# USB.net
KiCad netlist of a schematic drawn in Altium Designer
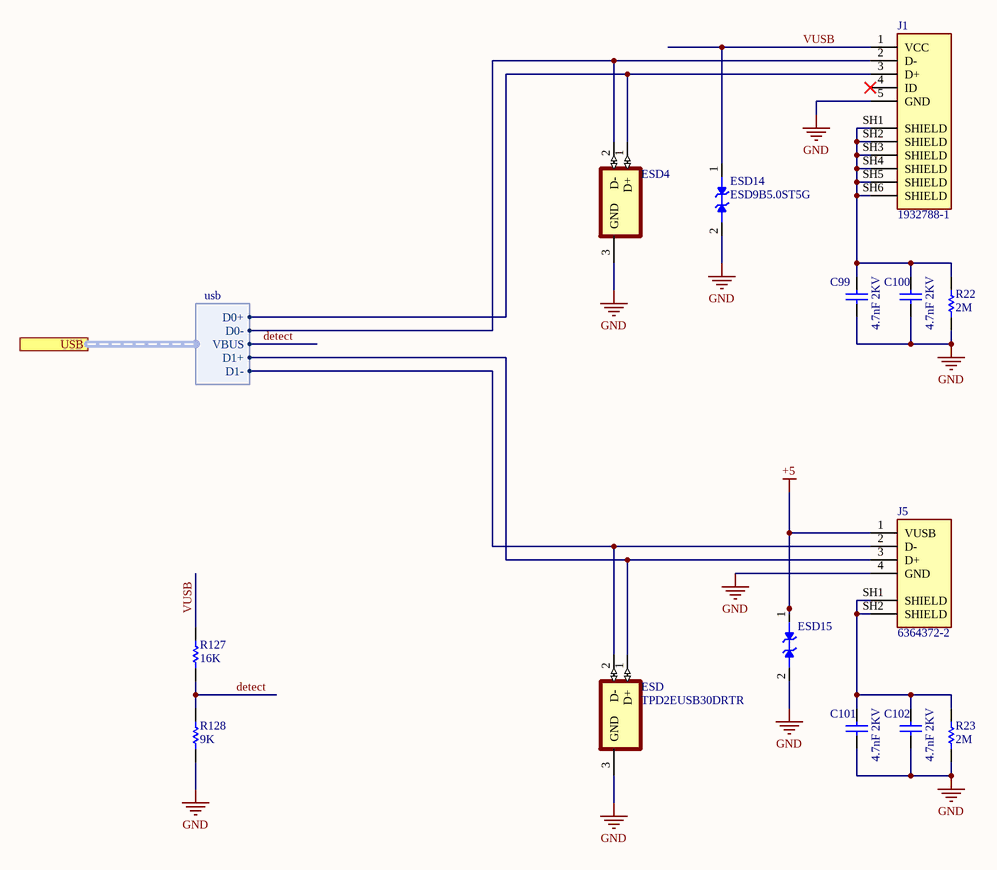
[diagram p0: USB.SchDoc]

(export (version "E")
  (design (tool "Eeschema 10.0.6"))
  (components
    (comp (ref "C99")
      (value "4.7nF 2KV")
      (footprint "C1210")
      (fields (field (name "Comment") "C1210"))
      (libsource (lib "kit") (part "C1210"))
    )
    (comp (ref "C100")
      (value "4.7nF 2KV")
      (footprint "C1210")
      (fields (field (name "Comment") "C1210"))
      (libsource (lib "kit") (part "C1210"))
    )
    (comp (ref "C101")
      (value "4.7nF 2KV")
      (footprint "C1210")
      (fields (field (name "Comment") "C1210"))
      (libsource (lib "kit") (part "C1210"))
    )
    (comp (ref "C102")
      (value "4.7nF 2KV")
      (footprint "C1210")
      (fields (field (name "Comment") "C1210"))
      (libsource (lib "kit") (part "C1210"))
    )
    (comp (ref "ESD")
      (value "TPD2EUSB30DRTR")
      (footprint "SOTFL35P100X50-3N")
      (description "2-channel ESD solution for SuperSpeed USB 3.0 interface 3-SOT-9X3 -40 to 85")
      (libsource (lib "kit") (part "TPD2EUSB30DRTR"))
    )
    (comp (ref "ESD4")
      (value "TPD2EUSB30DRTR")
      (footprint "SOTFL35P100X50-3N")
      (description "2-channel ESD solution for SuperSpeed USB 3.0 interface 3-SOT-9X3 -40 to 85")
      (libsource (lib "kit") (part "TPD2EUSB30DRTR"))
    )
    (comp (ref "ESD14")
      (value "ESD9B5.0ST5G")
      (footprint "SODFL1006X40N")
      (description "Clamp Ipp Tvs Diode Surface Mount SOD-923")
      (libsource (lib "kit") (part "ESD9B5.0ST5G"))
    )
    (comp (ref "ESD15")
      (value "ESD9B5.0ST5G")
      (footprint "SODFL1006X40N")
      (description "Clamp Ipp Tvs Diode Surface Mount SOD-923")
      (libsource (lib "kit") (part "ESD9B5.0ST5G"))
    )
    (comp (ref "J1")
      (value "1932788-1")
      (footprint "TE_1932788-1")
      (libsource (lib "kit") (part "1932788-1"))
    )
    (comp (ref "J5")
      (value "6364372-2")
      (footprint "TE_6364372-2")
      (libsource (lib "kit") (part "6364372-2"))
    )
    (comp (ref "R22")
      (value "2M")
      (footprint "R0603")
      (fields (field (name "Comment") "R0603"))
      (libsource (lib "kit") (part "R0603"))
    )
    (comp (ref "R23")
      (value "2M")
      (footprint "R0603")
      (fields (field (name "Comment") "R0603"))
      (libsource (lib "kit") (part "R0603"))
    )
    (comp (ref "R127")
      (value "16K")
      (footprint "R0603")
      (fields (field (name "Comment") "R0603"))
      (libsource (lib "kit") (part "R0603"))
    )
    (comp (ref "R128")
      (value "9K")
      (footprint "R0603")
      (fields (field (name "Comment") "R0603"))
      (libsource (lib "kit") (part "R0603"))
    )
  )
  (nets
    (net (code "2") (name "+5") (class "Default")
      (node (ref "ESD15") (pin "1") (pinfunction "A_1") (pintype "passive"))
      (node (ref "J5") (pin "1") (pinfunction "VUSB_1") (pintype "passive"))
    )
    (net (code "3") (name "/VUSB") (class "Default")
      (node (ref "ESD14") (pin "1") (pinfunction "A_1") (pintype "passive"))
      (node (ref "J1") (pin "1") (pinfunction "VCC_1") (pintype "power_in"))
      (node (ref "R127") (pin "2") (pinfunction "2_2") (pintype "passive"))
    )
    (net (code "4") (name "/detect") (class "Default")
      (node (ref "R127") (pin "1") (pinfunction "1_1") (pintype "passive"))
      (node (ref "R128") (pin "2") (pinfunction "2_2") (pintype "passive"))
    )
    (net (code "6") (name "GND") (class "Default")
      (node (ref "C100") (pin "1") (pinfunction "1_1") (pintype "passive"))
      (node (ref "C101") (pin "1") (pinfunction "1_1") (pintype "passive"))
      (node (ref "C102") (pin "1") (pinfunction "1_1") (pintype "passive"))
      (node (ref "C99") (pin "1") (pinfunction "1_1") (pintype "passive"))
      (node (ref "ESD") (pin "3") (pinfunction "GND_3") (pintype "power_in"))
      (node (ref "ESD14") (pin "2") (pinfunction "A1_2") (pintype "passive"))
      (node (ref "ESD15") (pin "2") (pinfunction "A1_2") (pintype "passive"))
      (node (ref "ESD4") (pin "3") (pinfunction "GND_3") (pintype "power_in"))
      (node (ref "J1") (pin "5") (pinfunction "GND_5") (pintype "power_in"))
      (node (ref "J5") (pin "4") (pinfunction "GND_4") (pintype "passive"))
      (node (ref "R128") (pin "1") (pinfunction "1_1") (pintype "passive"))
      (node (ref "R22") (pin "2") (pinfunction "2_2") (pintype "passive"))
      (node (ref "R23") (pin "2") (pinfunction "2_2") (pintype "passive"))
    )
    (net (code "7") (name "Net-(C100-Pad2)") (class "Default")
      (node (ref "C100") (pin "2") (pinfunction "2_2") (pintype "passive"))
      (node (ref "C99") (pin "2") (pinfunction "2_2") (pintype "passive"))
      (node (ref "J1") (pin "SH1") (pinfunction "SHIELD_SH1") (pintype "passive"))
      (node (ref "J1") (pin "SH2") (pinfunction "SHIELD_SH2") (pintype "passive"))
      (node (ref "J1") (pin "SH3") (pinfunction "SHIELD_SH3") (pintype "passive"))
      (node (ref "J1") (pin "SH4") (pinfunction "SHIELD_SH4") (pintype "passive"))
      (node (ref "J1") (pin "SH5") (pinfunction "SHIELD_SH5") (pintype "passive"))
      (node (ref "J1") (pin "SH6") (pinfunction "SHIELD_SH6") (pintype "passive"))
      (node (ref "R22") (pin "1") (pinfunction "1_1") (pintype "passive"))
    )
    (net (code "8") (name "Net-(C101-Pad2)") (class "Default")
      (node (ref "C101") (pin "2") (pinfunction "2_2") (pintype "passive"))
      (node (ref "C102") (pin "2") (pinfunction "2_2") (pintype "passive"))
      (node (ref "J5") (pin "SH1") (pinfunction "SHIELD_SH1") (pintype "passive"))
      (node (ref "J5") (pin "SH2") (pinfunction "SHIELD_SH2") (pintype "passive"))
      (node (ref "R23") (pin "1") (pinfunction "1_1") (pintype "passive"))
    )
    (net (code "9") (name "Net-(ESD-D+)") (class "Default")
      (node (ref "ESD") (pin "1") (pinfunction "D+_1") (pintype "bidirectional"))
      (node (ref "J5") (pin "3") (pinfunction "D+_3") (pintype "passive"))
    )
    (net (code "10") (name "Net-(ESD-D-)") (class "Default")
      (node (ref "ESD") (pin "2") (pinfunction "D-_2") (pintype "bidirectional"))
      (node (ref "J5") (pin "2") (pinfunction "D-_2") (pintype "passive"))
    )
    (net (code "11") (name "Net-(ESD4-D+)") (class "Default")
      (node (ref "ESD4") (pin "1") (pinfunction "D+_1") (pintype "bidirectional"))
      (node (ref "J1") (pin "3") (pinfunction "D+_3") (pintype "passive"))
    )
    (net (code "12") (name "Net-(ESD4-D-)") (class "Default")
      (node (ref "ESD4") (pin "2") (pinfunction "D-_2") (pintype "bidirectional"))
      (node (ref "J1") (pin "2") (pinfunction "D-_2") (pintype "passive"))
    )
    (net (code "13") (name "unconnected-(J1-ID-Pad4)") (class "Default")
      (node (ref "J1") (pin "4") (pinfunction "ID_4") (pintype "passive+no_connect"))
    )
  )
)
